# ST_link_V2_my-2.net
KiCad netlist of a schematic drawn in EAGLE
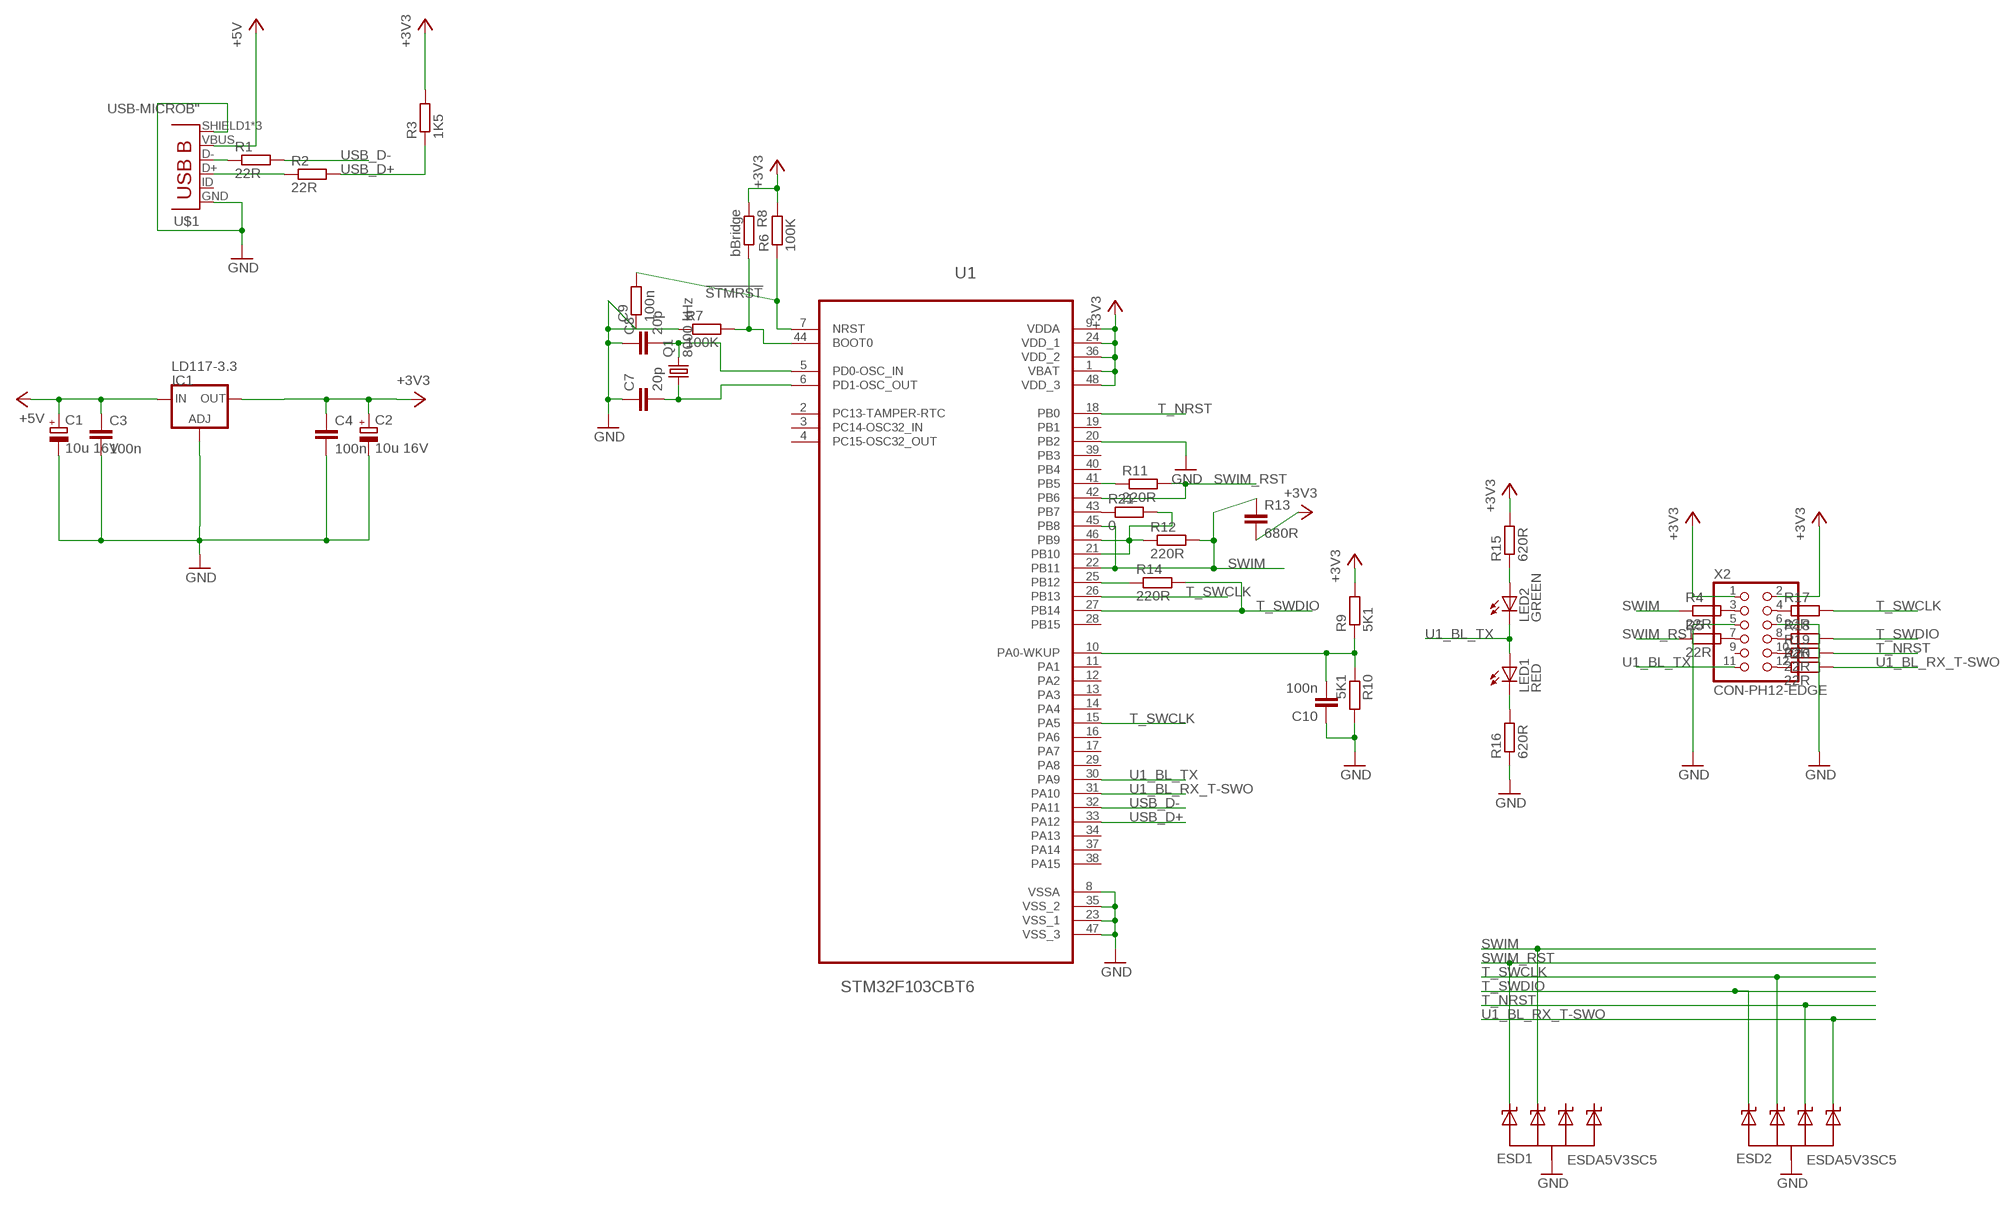
[diagram p0: schematic, sheet 1]

(export (version "E")
  (design (tool "Eeschema 10.0.6"))
  (components
    (comp (ref "C1")
      (value "10u 16V")
      (footprint "eagle-import:SMC_A")
      (libsource (lib "eagle-import") (part "CPOL-EUSMCA"))
    )
    (comp (ref "C2")
      (value "10u 16V")
      (footprint "eagle-import:SMC_A")
      (libsource (lib "eagle-import") (part "CPOL-EUSMCA"))
    )
    (comp (ref "C3")
      (value "100n")
      (footprint "eagle-import:C0805")
      (libsource (lib "eagle-import") (part "CAP_0805"))
    )
    (comp (ref "C4")
      (value "100n")
      (footprint "eagle-import:C0805")
      (libsource (lib "eagle-import") (part "CAP_0805"))
    )
    (comp (ref "C7")
      (value "20p")
      (footprint "eagle-import:C0805")
      (libsource (lib "eagle-import") (part "CAP_0805"))
    )
    (comp (ref "C8")
      (value "20p")
      (footprint "eagle-import:C0805")
      (libsource (lib "eagle-import") (part "CAP_0805"))
    )
    (comp (ref "C9")
      (value "100n")
      (footprint "eagle-import:R0805")
      (libsource (lib "eagle-import") (part "R_0805"))
    )
    (comp (ref "C10")
      (value "100n")
      (footprint "eagle-import:C0805")
      (libsource (lib "eagle-import") (part "CAP_0805"))
    )
    (comp (ref "ESD1")
      (value "ESDA5V3SC5")
      (footprint "eagle-import:SOT23-5L")
      (libsource (lib "eagle-import") (part "ESDAXXSC5"))
    )
    (comp (ref "ESD2")
      (value "ESDA5V3SC5")
      (footprint "eagle-import:SOT23-5L")
      (libsource (lib "eagle-import") (part "ESDAXXSC5"))
    )
    (comp (ref "IC1")
      (value "LD117-3.3")
      (footprint "eagle-import:SOT223")
      (libsource (lib "eagle-import") (part "LD117A?STR"))
    )
    (comp (ref "LED1")
      (value "RED")
      (footprint "eagle-import:CHIPLED_1206")
      (libsource (lib "eagle-import") (part "LEDCHIPLED_1206"))
    )
    (comp (ref "LED2")
      (value "GREEN")
      (footprint "eagle-import:CHIPLED_1206")
      (libsource (lib "eagle-import") (part "LEDCHIPLED_1206"))
    )
    (comp (ref "Q1")
      (value "8000 kHz")
      (footprint "eagle-import:HC49UP")
      (libsource (lib "eagle-import") (part "CRYSTALHC49UP"))
    )
    (comp (ref "R1")
      (value "22R")
      (footprint "eagle-import:R0805")
      (libsource (lib "eagle-import") (part "R_0805"))
    )
    (comp (ref "R2")
      (value "22R")
      (footprint "eagle-import:R0805")
      (libsource (lib "eagle-import") (part "R_0805"))
    )
    (comp (ref "R3")
      (value "1K5")
      (footprint "eagle-import:R0805")
      (libsource (lib "eagle-import") (part "R_0805"))
    )
    (comp (ref "R4")
      (value "22R")
      (footprint "eagle-import:R0805")
      (libsource (lib "eagle-import") (part "R_0805"))
    )
    (comp (ref "R5")
      (value "22R")
      (footprint "eagle-import:R0805")
      (libsource (lib "eagle-import") (part "R_0805"))
    )
    (comp (ref "R6")
      (value "100K")
      (footprint "eagle-import:R0805")
      (libsource (lib "eagle-import") (part "R_0805"))
    )
    (comp (ref "R7")
      (value "100K")
      (footprint "eagle-import:R0805")
      (libsource (lib "eagle-import") (part "R_0805"))
    )
    (comp (ref "R8")
      (value "bBridge")
      (footprint "eagle-import:R0805")
      (libsource (lib "eagle-import") (part "R_0805"))
    )
    (comp (ref "R9")
      (value "5K1")
      (footprint "eagle-import:R0603")
      (libsource (lib "eagle-import") (part "R_0603"))
    )
    (comp (ref "R10")
      (value "5K1")
      (footprint "eagle-import:R0603")
      (libsource (lib "eagle-import") (part "R_0603"))
    )
    (comp (ref "R11")
      (value "220R")
      (footprint "eagle-import:R0805")
      (libsource (lib "eagle-import") (part "R_0805"))
    )
    (comp (ref "R12")
      (value "220R")
      (footprint "eagle-import:R0805")
      (libsource (lib "eagle-import") (part "R_0805"))
    )
    (comp (ref "R13")
      (value "680R")
      (footprint "eagle-import:C0805")
      (libsource (lib "eagle-import") (part "CAP_0805"))
    )
    (comp (ref "R14")
      (value "220R")
      (footprint "eagle-import:R0805")
      (libsource (lib "eagle-import") (part "R_0805"))
    )
    (comp (ref "R15")
      (value "620R")
      (footprint "eagle-import:R0805")
      (libsource (lib "eagle-import") (part "R_0805"))
    )
    (comp (ref "R16")
      (value "620R")
      (footprint "eagle-import:R0805")
      (libsource (lib "eagle-import") (part "R_0805"))
    )
    (comp (ref "R17")
      (value "22R")
      (footprint "eagle-import:R0805")
      (libsource (lib "eagle-import") (part "R_0805"))
    )
    (comp (ref "R18")
      (value "22R")
      (footprint "eagle-import:R0805")
      (libsource (lib "eagle-import") (part "R_0805"))
    )
    (comp (ref "R19")
      (value "22R")
      (footprint "eagle-import:R0805")
      (libsource (lib "eagle-import") (part "R_0805"))
    )
    (comp (ref "R20")
      (value "22R")
      (footprint "eagle-import:R0805")
      (libsource (lib "eagle-import") (part "R_0805"))
    )
    (comp (ref "R21")
      (value "0")
      (footprint "eagle-import:R0805")
      (libsource (lib "eagle-import") (part "R_0805"))
    )
    (comp (ref "U$1")
      (value "USB-MICROB\"")
      (footprint "eagle-import:USB-B-MICRO-SMD_V03")
      (libsource (lib "eagle-import") (part "USB-MICROB{dblquote}"))
    )
    (comp (ref "U1")
      (value "STM32F103CBT6")
      (footprint "eagle-import:QFP50P900X900X160-48N")
      (libsource (lib "eagle-import") (part "STM32F103CBT6"))
    )
    (comp (ref "X2")
      (value "CON-PH12-EDGE")
      (footprint "eagle-import:ML12_EDGE_SMD")
      (libsource (lib "eagle-import") (part "CON-PH12-EDGE"))
    )
  )
  (nets
    (net (code "1") (name "+3V3") (class "Default")
      (node (ref "C2") (pin "+") (pinfunction "+_+") (pintype "passive"))
      (node (ref "C4") (pin "1") (pinfunction "1_1") (pintype "passive"))
      (node (ref "IC1") (pin "4") (pinfunction "OUT_4") (pintype "passive"))
      (node (ref "R13") (pin "2") (pinfunction "2_2") (pintype "passive"))
      (node (ref "R15") (pin "2") (pinfunction "2_2") (pintype "passive"))
      (node (ref "R3") (pin "2") (pinfunction "2_2") (pintype "passive"))
      (node (ref "R6") (pin "2") (pinfunction "2_2") (pintype "passive"))
      (node (ref "R8") (pin "1") (pinfunction "1_1") (pintype "passive"))
      (node (ref "R9") (pin "2") (pinfunction "2_2") (pintype "passive"))
      (node (ref "U1") (pin "1") (pinfunction "VBAT_1") (pintype "input"))
      (node (ref "U1") (pin "24") (pinfunction "VDD_1_24") (pintype "bidirectional"))
      (node (ref "U1") (pin "36") (pinfunction "VDD_2_36") (pintype "power_in"))
      (node (ref "U1") (pin "48") (pinfunction "VDD_3_48") (pintype "power_in"))
      (node (ref "U1") (pin "9") (pinfunction "VDDA_9") (pintype "power_in"))
      (node (ref "X2") (pin "1") (pinfunction "1_1") (pintype "passive"))
      (node (ref "X2") (pin "2") (pinfunction "2_2") (pintype "passive"))
    )
    (net (code "2") (name "+5V") (class "Default")
      (node (ref "C1") (pin "+") (pinfunction "+_+") (pintype "passive"))
      (node (ref "C3") (pin "1") (pinfunction "1_1") (pintype "passive"))
      (node (ref "IC1") (pin "3") (pinfunction "IN_3") (pintype "input"))
      (node (ref "U$1") (pin "VBUS") (pinfunction "VBUS_VBUS") (pintype "bidirectional"))
    )
    (net (code "3") (name "/SWIM") (class "Default")
      (node (ref "ESD1") (pin "3") (pinfunction "C2_3") (pintype "passive"))
      (node (ref "R12") (pin "2") (pinfunction "2_2") (pintype "passive"))
      (node (ref "R13") (pin "1") (pinfunction "1_1") (pintype "passive"))
      (node (ref "R4") (pin "1") (pinfunction "1_1") (pintype "passive"))
      (node (ref "U1") (pin "22") (pinfunction "PB11_22") (pintype "bidirectional"))
      (node (ref "U1") (pin "45") (pinfunction "PB8_45") (pintype "bidirectional"))
    )
    (net (code "4") (name "/SWIM_RST") (class "Default")
      (node (ref "ESD1") (pin "1") (pinfunction "C1_1") (pintype "passive"))
      (node (ref "R11") (pin "2") (pinfunction "2_2") (pintype "passive"))
      (node (ref "R5") (pin "1") (pinfunction "1_1") (pintype "passive"))
      (node (ref "U1") (pin "42") (pinfunction "PB6_42") (pintype "bidirectional"))
    )
    (net (code "5") (name "/T_NRST") (class "Default")
      (node (ref "ESD2") (pin "4") (pinfunction "C3_4") (pintype "passive"))
      (node (ref "R19") (pin "2") (pinfunction "2_2") (pintype "passive"))
      (node (ref "U1") (pin "18") (pinfunction "PB0_18") (pintype "bidirectional"))
    )
    (net (code "6") (name "/T_SWCLK") (class "Default")
      (node (ref "ESD2") (pin "3") (pinfunction "C2_3") (pintype "passive"))
      (node (ref "R17") (pin "2") (pinfunction "2_2") (pintype "passive"))
      (node (ref "U1") (pin "15") (pinfunction "PA5_15") (pintype "bidirectional"))
      (node (ref "U1") (pin "26") (pinfunction "PB13_26") (pintype "bidirectional"))
    )
    (net (code "7") (name "/T_SWDIO") (class "Default")
      (node (ref "ESD2") (pin "1") (pinfunction "C1_1") (pintype "passive"))
      (node (ref "R14") (pin "2") (pinfunction "2_2") (pintype "passive"))
      (node (ref "R18") (pin "2") (pinfunction "2_2") (pintype "passive"))
      (node (ref "U1") (pin "27") (pinfunction "PB14_27") (pintype "bidirectional"))
    )
    (net (code "8") (name "/U1_BL_RX_T-SWO") (class "Default")
      (node (ref "ESD2") (pin "5") (pinfunction "C4_5") (pintype "passive"))
      (node (ref "R20") (pin "2") (pinfunction "2_2") (pintype "passive"))
      (node (ref "U1") (pin "31") (pinfunction "PA10_31") (pintype "bidirectional"))
    )
    (net (code "9") (name "/U1_BL_TX") (class "Default")
      (node (ref "LED1") (pin "A") (pinfunction "A_A") (pintype "passive"))
      (node (ref "LED2") (pin "C") (pinfunction "C_C") (pintype "passive"))
      (node (ref "U1") (pin "30") (pinfunction "PA9_30") (pintype "bidirectional"))
      (node (ref "X2") (pin "11") (pinfunction "11_11") (pintype "passive"))
    )
    (net (code "10") (name "/USB_D+") (class "Default")
      (node (ref "R2") (pin "2") (pinfunction "2_2") (pintype "passive"))
      (node (ref "R3") (pin "1") (pinfunction "1_1") (pintype "passive"))
      (node (ref "U1") (pin "33") (pinfunction "PA12_33") (pintype "bidirectional"))
    )
    (net (code "11") (name "/USB_D-") (class "Default")
      (node (ref "R1") (pin "2") (pinfunction "2_2") (pintype "passive"))
      (node (ref "U1") (pin "32") (pinfunction "PA11_32") (pintype "power_in"))
    )
    (net (code "12") (name "/~{STMRST}") (class "Default")
      (node (ref "C9") (pin "2") (pinfunction "2_2") (pintype "passive"))
      (node (ref "R6") (pin "1") (pinfunction "1_1") (pintype "passive"))
      (node (ref "U1") (pin "7") (pinfunction "NRST_7") (pintype "bidirectional"))
    )
    (net (code "13") (name "GND") (class "Default")
      (node (ref "C1") (pin "-") (pinfunction "-_-") (pintype "passive"))
      (node (ref "C10") (pin "1") (pinfunction "1_1") (pintype "passive"))
      (node (ref "C2") (pin "-") (pinfunction "-_-") (pintype "passive"))
      (node (ref "C3") (pin "2") (pinfunction "2_2") (pintype "passive"))
      (node (ref "C4") (pin "2") (pinfunction "2_2") (pintype "passive"))
      (node (ref "C7") (pin "1") (pinfunction "1_1") (pintype "passive"))
      (node (ref "C8") (pin "1") (pinfunction "1_1") (pintype "passive"))
      (node (ref "C9") (pin "1") (pinfunction "1_1") (pintype "passive"))
      (node (ref "ESD1") (pin "2") (pinfunction "A_2") (pintype "passive"))
      (node (ref "ESD2") (pin "2") (pinfunction "A_2") (pintype "passive"))
      (node (ref "IC1") (pin "1") (pinfunction "ADJ_1") (pintype "input"))
      (node (ref "R10") (pin "2") (pinfunction "2_2") (pintype "passive"))
      (node (ref "R16") (pin "1") (pinfunction "1_1") (pintype "passive"))
      (node (ref "R7") (pin "1") (pinfunction "1_1") (pintype "passive"))
      (node (ref "U$1") (pin "GND") (pinfunction "GND_GND") (pintype "bidirectional"))
      (node (ref "U$1") (pin "SHIELD1") (pinfunction "SHIELD_SHIELD1") (pintype "bidirectional"))
      (node (ref "U$1") (pin "SHIELD2") (pinfunction "SHIELD_SHIELD2") (pintype "bidirectional"))
      (node (ref "U$1") (pin "SHIELD3") (pinfunction "SHIELD_SHIELD3") (pintype "bidirectional"))
      (node (ref "U1") (pin "20") (pinfunction "PB2_20") (pintype "bidirectional"))
      (node (ref "U1") (pin "23") (pinfunction "VSS_1_23") (pintype "bidirectional"))
      (node (ref "U1") (pin "35") (pinfunction "VSS_2_35") (pintype "passive"))
      (node (ref "U1") (pin "47") (pinfunction "VSS_3_47") (pintype "passive"))
      (node (ref "U1") (pin "8") (pinfunction "VSSA_8") (pintype "passive"))
      (node (ref "X2") (pin "5") (pinfunction "5_5") (pintype "passive"))
      (node (ref "X2") (pin "6") (pinfunction "6_6") (pintype "passive"))
    )
    (net (code "14") (name "Net-(LED1-PadC)") (class "Default")
      (node (ref "LED1") (pin "C") (pinfunction "C_C") (pintype "passive"))
      (node (ref "R16") (pin "2") (pinfunction "2_2") (pintype "passive"))
    )
    (net (code "15") (name "Net-(LED2-PadA)") (class "Default")
      (node (ref "LED2") (pin "A") (pinfunction "A_A") (pintype "passive"))
      (node (ref "R15") (pin "1") (pinfunction "1_1") (pintype "passive"))
    )
    (net (code "16") (name "Net-(R1-Pad1)") (class "Default")
      (node (ref "R1") (pin "1") (pinfunction "1_1") (pintype "passive"))
      (node (ref "U$1") (pin "D-") (pinfunction "D-_D-") (pintype "bidirectional"))
    )
    (net (code "17") (name "Net-(R2-Pad1)") (class "Default")
      (node (ref "R2") (pin "1") (pinfunction "1_1") (pintype "passive"))
      (node (ref "U$1") (pin "D+") (pinfunction "D+_D+") (pintype "bidirectional"))
    )
    (net (code "18") (name "Net-(R4-Pad2)") (class "Default")
      (node (ref "R4") (pin "2") (pinfunction "2_2") (pintype "passive"))
      (node (ref "X2") (pin "3") (pinfunction "3_3") (pintype "passive"))
    )
    (net (code "19") (name "Net-(R5-Pad2)") (class "Default")
      (node (ref "R5") (pin "2") (pinfunction "2_2") (pintype "passive"))
      (node (ref "X2") (pin "7") (pinfunction "7_7") (pintype "passive"))
    )
    (net (code "20") (name "Net-(R17-Pad1)") (class "Default")
      (node (ref "R17") (pin "1") (pinfunction "1_1") (pintype "passive"))
      (node (ref "X2") (pin "4") (pinfunction "4_4") (pintype "passive"))
    )
    (net (code "21") (name "Net-(R18-Pad1)") (class "Default")
      (node (ref "R18") (pin "1") (pinfunction "1_1") (pintype "passive"))
      (node (ref "X2") (pin "8") (pinfunction "8_8") (pintype "passive"))
    )
    (net (code "22") (name "Net-(R19-Pad1)") (class "Default")
      (node (ref "R19") (pin "1") (pinfunction "1_1") (pintype "passive"))
      (node (ref "X2") (pin "10") (pinfunction "10_10") (pintype "passive"))
    )
    (net (code "23") (name "Net-(R20-Pad1)") (class "Default")
      (node (ref "R20") (pin "1") (pinfunction "1_1") (pintype "passive"))
      (node (ref "X2") (pin "12") (pinfunction "12_12") (pintype "passive"))
    )
    (net (code "24") (name "Net-(U1-BOOT0)") (class "Default")
      (node (ref "R7") (pin "2") (pinfunction "2_2") (pintype "passive"))
      (node (ref "R8") (pin "2") (pinfunction "2_2") (pintype "passive"))
      (node (ref "U1") (pin "44") (pinfunction "BOOT0_44") (pintype "bidirectional"))
    )
    (net (code "25") (name "Net-(U1-PA0-WKUP)") (class "Default")
      (node (ref "C10") (pin "2") (pinfunction "2_2") (pintype "passive"))
      (node (ref "R10") (pin "1") (pinfunction "1_1") (pintype "passive"))
      (node (ref "R9") (pin "1") (pinfunction "1_1") (pintype "passive"))
      (node (ref "U1") (pin "10") (pinfunction "PA0-WKUP_10") (pintype "bidirectional"))
    )
    (net (code "26") (name "Net-(U1-PB5)") (class "Default")
      (node (ref "R11") (pin "1") (pinfunction "1_1") (pintype "passive"))
      (node (ref "U1") (pin "41") (pinfunction "PB5_41") (pintype "bidirectional"))
    )
    (net (code "27") (name "Net-(U1-PB7)") (class "Default")
      (node (ref "R21") (pin "1") (pinfunction "1_1") (pintype "passive"))
      (node (ref "U1") (pin "43") (pinfunction "PB7_43") (pintype "bidirectional"))
    )
    (net (code "28") (name "Net-(U1-PB10)") (class "Default")
      (node (ref "R12") (pin "1") (pinfunction "1_1") (pintype "passive"))
      (node (ref "R21") (pin "2") (pinfunction "2_2") (pintype "passive"))
      (node (ref "U1") (pin "21") (pinfunction "PB10_21") (pintype "bidirectional"))
      (node (ref "U1") (pin "46") (pinfunction "PB9_46") (pintype "bidirectional"))
    )
    (net (code "29") (name "Net-(U1-PB12)") (class "Default")
      (node (ref "R14") (pin "1") (pinfunction "1_1") (pintype "passive"))
      (node (ref "U1") (pin "25") (pinfunction "PB12_25") (pintype "bidirectional"))
    )
    (net (code "30") (name "Net-(U1-PD0-OSC_IN)") (class "Default")
      (node (ref "C8") (pin "2") (pinfunction "2_2") (pintype "passive"))
      (node (ref "Q1") (pin "2") (pinfunction "2_2") (pintype "passive"))
      (node (ref "U1") (pin "5") (pinfunction "PD0-OSC_IN_5") (pintype "bidirectional"))
    )
    (net (code "31") (name "Net-(U1-PD1-OSC_OUT)") (class "Default")
      (node (ref "C7") (pin "2") (pinfunction "2_2") (pintype "passive"))
      (node (ref "Q1") (pin "1") (pinfunction "1_1") (pintype "passive"))
      (node (ref "U1") (pin "6") (pinfunction "PD1-OSC_OUT_6") (pintype "bidirectional"))
    )
    (net (code "32") (name "unconnected-(ESD1-C3-Pad4)") (class "Default")
      (node (ref "ESD1") (pin "4") (pinfunction "C3_4") (pintype "passive"))
    )
    (net (code "33") (name "unconnected-(ESD1-C4-Pad5)") (class "Default")
      (node (ref "ESD1") (pin "5") (pinfunction "C4_5") (pintype "passive"))
    )
    (net (code "34") (name "unconnected-(U$1-USBID-PadID)") (class "Default")
      (node (ref "U$1") (pin "ID") (pinfunction "USBID_ID") (pintype "bidirectional"))
    )
    (net (code "35") (name "unconnected-(U1-PA1-Pad11)") (class "Default")
      (node (ref "U1") (pin "11") (pinfunction "PA1_11") (pintype "bidirectional"))
    )
    (net (code "36") (name "unconnected-(U1-PA2-Pad12)") (class "Default")
      (node (ref "U1") (pin "12") (pinfunction "PA2_12") (pintype "bidirectional"))
    )
    (net (code "37") (name "unconnected-(U1-PA3-Pad13)") (class "Default")
      (node (ref "U1") (pin "13") (pinfunction "PA3_13") (pintype "bidirectional"))
    )
    (net (code "38") (name "unconnected-(U1-PA4-Pad14)") (class "Default")
      (node (ref "U1") (pin "14") (pinfunction "PA4_14") (pintype "bidirectional"))
    )
    (net (code "39") (name "unconnected-(U1-PA6-Pad16)") (class "Default")
      (node (ref "U1") (pin "16") (pinfunction "PA6_16") (pintype "bidirectional"))
    )
    (net (code "40") (name "unconnected-(U1-PA7-Pad17)") (class "Default")
      (node (ref "U1") (pin "17") (pinfunction "PA7_17") (pintype "bidirectional"))
    )
    (net (code "41") (name "unconnected-(U1-PA8-Pad29)") (class "Default")
      (node (ref "U1") (pin "29") (pinfunction "PA8_29") (pintype "bidirectional"))
    )
    (net (code "42") (name "unconnected-(U1-PA13-Pad34)") (class "Default")
      (node (ref "U1") (pin "34") (pinfunction "PA13_34") (pintype "bidirectional"))
    )
    (net (code "43") (name "unconnected-(U1-PA14-Pad37)") (class "Default")
      (node (ref "U1") (pin "37") (pinfunction "PA14_37") (pintype "bidirectional"))
    )
    (net (code "44") (name "unconnected-(U1-PA15-Pad38)") (class "Default")
      (node (ref "U1") (pin "38") (pinfunction "PA15_38") (pintype "bidirectional"))
    )
    (net (code "45") (name "unconnected-(U1-PB1-Pad19)") (class "Default")
      (node (ref "U1") (pin "19") (pinfunction "PB1_19") (pintype "bidirectional"))
    )
    (net (code "46") (name "unconnected-(U1-PB3-Pad39)") (class "Default")
      (node (ref "U1") (pin "39") (pinfunction "PB3_39") (pintype "bidirectional"))
    )
    (net (code "47") (name "unconnected-(U1-PB4-Pad40)") (class "Default")
      (node (ref "U1") (pin "40") (pinfunction "PB4_40") (pintype "bidirectional"))
    )
    (net (code "48") (name "unconnected-(U1-PB15-Pad28)") (class "Default")
      (node (ref "U1") (pin "28") (pinfunction "PB15_28") (pintype "bidirectional"))
    )
    (net (code "49") (name "unconnected-(U1-PC13-TAMPER-RTC-Pad2)") (class "Default")
      (node (ref "U1") (pin "2") (pinfunction "PC13-TAMPER-RTC_2") (pintype "bidirectional"))
    )
    (net (code "50") (name "unconnected-(U1-PC14-OSC32_IN-Pad3)") (class "Default")
      (node (ref "U1") (pin "3") (pinfunction "PC14-OSC32_IN_3") (pintype "bidirectional"))
    )
    (net (code "51") (name "unconnected-(U1-PC15-OSC32_OUT-Pad4)") (class "Default")
      (node (ref "U1") (pin "4") (pinfunction "PC15-OSC32_OUT_4") (pintype "bidirectional"))
    )
    (net (code "52") (name "unconnected-(X2-Pad9)") (class "Default")
      (node (ref "X2") (pin "9") (pinfunction "9_9") (pintype "passive"))
    )
  )
)
